# First_Board.net
KiCad netlist of a schematic drawn in EAGLE
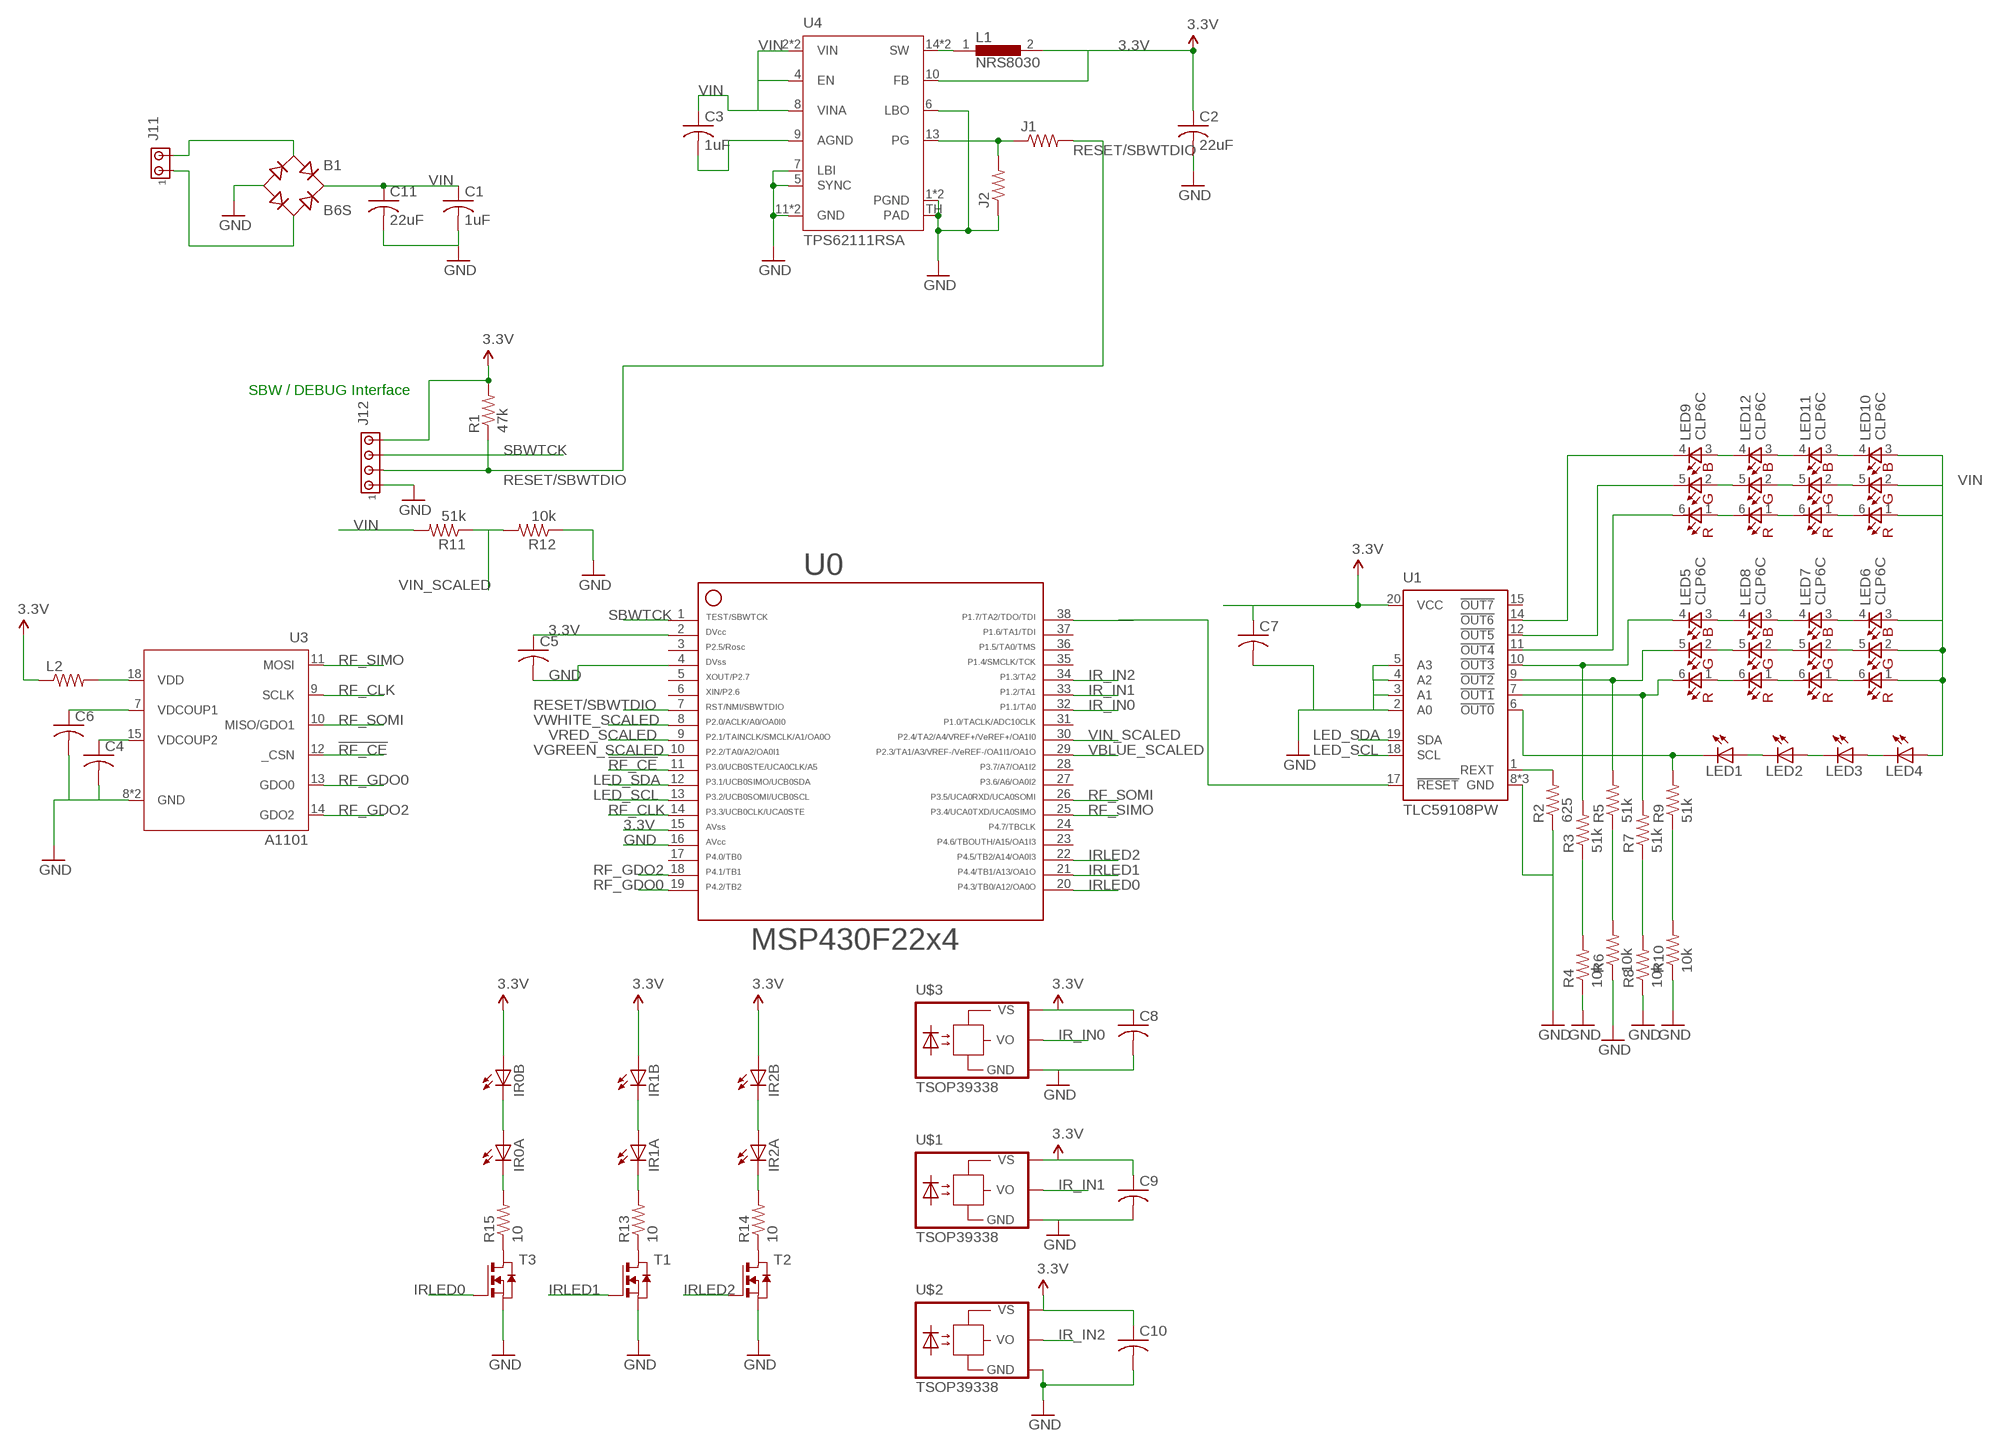
[diagram p0: schematic, sheet 1]

(export (version "E")
  (design (tool "Eeschema 10.0.6"))
  (components
    (comp (ref "B1")
      (value "B6S")
      (footprint "eagle-import:MBS")
      (libsource (lib "eagle-import") (part "BS6"))
    )
    (comp (ref "C1")
      (value "1uF")
      (footprint "eagle-import:C0805")
      (libsource (lib "eagle-import") (part "C-USC0805"))
    )
    (comp (ref "C2")
      (value "22uF")
      (footprint "eagle-import:C0805")
      (libsource (lib "eagle-import") (part "C-USC0805"))
    )
    (comp (ref "C3")
      (value "1uF")
      (footprint "eagle-import:C0603")
      (libsource (lib "eagle-import") (part "C-USC0603"))
    )
    (comp (ref "C4")
      (value "C-USC0603")
      (footprint "eagle-import:C0603")
      (libsource (lib "eagle-import") (part "C-USC0603"))
    )
    (comp (ref "C5")
      (value "C-USC0603")
      (footprint "eagle-import:C0603")
      (libsource (lib "eagle-import") (part "C-USC0603"))
    )
    (comp (ref "C6")
      (value "C-USC0603")
      (footprint "eagle-import:C0603")
      (libsource (lib "eagle-import") (part "C-USC0603"))
    )
    (comp (ref "C7")
      (value "C-USC0603")
      (footprint "eagle-import:C0603")
      (libsource (lib "eagle-import") (part "C-USC0603"))
    )
    (comp (ref "C8")
      (value "C-USC0603")
      (footprint "eagle-import:C0603")
      (libsource (lib "eagle-import") (part "C-USC0603"))
    )
    (comp (ref "C9")
      (value "C-USC0603")
      (footprint "eagle-import:C0603")
      (libsource (lib "eagle-import") (part "C-USC0603"))
    )
    (comp (ref "C10")
      (value "C-USC0603")
      (footprint "eagle-import:C0603")
      (libsource (lib "eagle-import") (part "C-USC0603"))
    )
    (comp (ref "C11")
      (value "22uF")
      (footprint "eagle-import:C1210")
      (libsource (lib "eagle-import") (part "C-USC1210"))
    )
    (comp (ref "IR0A")
      (value "LED5MM")
      (footprint "eagle-import:LED5MM")
      (libsource (lib "eagle-import") (part "LED5MM"))
    )
    (comp (ref "IR0B")
      (value "LED5MM")
      (footprint "eagle-import:LED5MM")
      (libsource (lib "eagle-import") (part "LED5MM"))
    )
    (comp (ref "IR1A")
      (value "LED5MM")
      (footprint "eagle-import:LED5MM")
      (libsource (lib "eagle-import") (part "LED5MM"))
    )
    (comp (ref "IR1B")
      (value "LED5MM")
      (footprint "eagle-import:LED5MM")
      (libsource (lib "eagle-import") (part "LED5MM"))
    )
    (comp (ref "IR2A")
      (value "LED5MM")
      (footprint "eagle-import:LED5MM")
      (libsource (lib "eagle-import") (part "LED5MM"))
    )
    (comp (ref "IR2B")
      (value "LED5MM")
      (footprint "eagle-import:LED5MM")
      (libsource (lib "eagle-import") (part "LED5MM"))
    )
    (comp (ref "J1")
      (value "R-US_R0603")
      (footprint "eagle-import:R0603")
      (libsource (lib "eagle-import") (part "R-US_R0603"))
    )
    (comp (ref "J2")
      (value "R-US_R0603")
      (footprint "eagle-import:R0603")
      (libsource (lib "eagle-import") (part "R-US_R0603"))
    )
    (comp (ref "J11")
      (value "MTA02-100")
      (footprint "eagle-import:10X02MTA")
      (libsource (lib "eagle-import") (part "MTA02-100"))
    )
    (comp (ref "J12")
      (value "MTA04-100")
      (footprint "eagle-import:10X04MTA")
      (libsource (lib "eagle-import") (part "MTA04-100"))
    )
    (comp (ref "L1")
      (value "NRS8030")
      (footprint "eagle-import:NRS8030")
      (libsource (lib "eagle-import") (part "NRS8030"))
    )
    (comp (ref "L2")
      (value "R-US_R0603")
      (footprint "eagle-import:R0603")
      (libsource (lib "eagle-import") (part "R-US_R0603"))
    )
    (comp (ref "LED1")
      (value "LED-2AC-SUPERFLUX")
      (footprint "eagle-import:SUPERFLUX-7.6X7.6")
      (libsource (lib "eagle-import") (part "LED-2AC-SUPERFLUX"))
    )
    (comp (ref "LED2")
      (value "LED-2AC-SUPERFLUX")
      (footprint "eagle-import:SUPERFLUX-7.6X7.6")
      (libsource (lib "eagle-import") (part "LED-2AC-SUPERFLUX"))
    )
    (comp (ref "LED3")
      (value "LED-2AC-SUPERFLUX")
      (footprint "eagle-import:SUPERFLUX-7.6X7.6")
      (libsource (lib "eagle-import") (part "LED-2AC-SUPERFLUX"))
    )
    (comp (ref "LED4")
      (value "LED-2AC-SUPERFLUX")
      (footprint "eagle-import:SUPERFLUX-7.6X7.6")
      (libsource (lib "eagle-import") (part "LED-2AC-SUPERFLUX"))
    )
    (comp (ref "LED5")
      (value "CLP6C")
      (footprint "eagle-import:CLP6C")
      (libsource (lib "eagle-import") (part "CLP6C"))
    )
    (comp (ref "LED6")
      (value "CLP6C")
      (footprint "eagle-import:CLP6C")
      (libsource (lib "eagle-import") (part "CLP6C"))
    )
    (comp (ref "LED7")
      (value "CLP6C")
      (footprint "eagle-import:CLP6C")
      (libsource (lib "eagle-import") (part "CLP6C"))
    )
    (comp (ref "LED8")
      (value "CLP6C")
      (footprint "eagle-import:CLP6C")
      (libsource (lib "eagle-import") (part "CLP6C"))
    )
    (comp (ref "LED9")
      (value "CLP6C")
      (footprint "eagle-import:CLP6C")
      (libsource (lib "eagle-import") (part "CLP6C"))
    )
    (comp (ref "LED10")
      (value "CLP6C")
      (footprint "eagle-import:CLP6C")
      (libsource (lib "eagle-import") (part "CLP6C"))
    )
    (comp (ref "LED11")
      (value "CLP6C")
      (footprint "eagle-import:CLP6C")
      (libsource (lib "eagle-import") (part "CLP6C"))
    )
    (comp (ref "LED12")
      (value "CLP6C")
      (footprint "eagle-import:CLP6C")
      (libsource (lib "eagle-import") (part "CLP6C"))
    )
    (comp (ref "R1")
      (value "47k")
      (footprint "eagle-import:R0603")
      (libsource (lib "eagle-import") (part "R-US_R0603"))
    )
    (comp (ref "R2")
      (value "625")
      (footprint "eagle-import:R0603")
      (libsource (lib "eagle-import") (part "R-US_R0603"))
    )
    (comp (ref "R3")
      (value "51k")
      (footprint "eagle-import:R0603")
      (libsource (lib "eagle-import") (part "R-US_R0603"))
    )
    (comp (ref "R4")
      (value "10k")
      (footprint "eagle-import:R0603")
      (libsource (lib "eagle-import") (part "R-US_R0603"))
    )
    (comp (ref "R5")
      (value "51k")
      (footprint "eagle-import:R0603")
      (libsource (lib "eagle-import") (part "R-US_R0603"))
    )
    (comp (ref "R6")
      (value "10k")
      (footprint "eagle-import:R0603")
      (libsource (lib "eagle-import") (part "R-US_R0603"))
    )
    (comp (ref "R7")
      (value "51k")
      (footprint "eagle-import:R0603")
      (libsource (lib "eagle-import") (part "R-US_R0603"))
    )
    (comp (ref "R8")
      (value "10k")
      (footprint "eagle-import:R0603")
      (libsource (lib "eagle-import") (part "R-US_R0603"))
    )
    (comp (ref "R9")
      (value "51k")
      (footprint "eagle-import:R0603")
      (libsource (lib "eagle-import") (part "R-US_R0603"))
    )
    (comp (ref "R10")
      (value "10k")
      (footprint "eagle-import:R0603")
      (libsource (lib "eagle-import") (part "R-US_R0603"))
    )
    (comp (ref "R11")
      (value "51k")
      (footprint "eagle-import:R0603")
      (libsource (lib "eagle-import") (part "R-US_R0603"))
    )
    (comp (ref "R12")
      (value "10k")
      (footprint "eagle-import:R0603")
      (libsource (lib "eagle-import") (part "R-US_R0603"))
    )
    (comp (ref "R13")
      (value "10")
      (footprint "eagle-import:R0603")
      (libsource (lib "eagle-import") (part "R-US_R0603"))
    )
    (comp (ref "R14")
      (value "10")
      (footprint "eagle-import:R0603")
      (libsource (lib "eagle-import") (part "R-US_R0603"))
    )
    (comp (ref "R15")
      (value "10")
      (footprint "eagle-import:R0603")
      (libsource (lib "eagle-import") (part "R-US_R0603"))
    )
    (comp (ref "T1")
      (value "NMOSSOT23")
      (footprint "eagle-import:SOT-23")
      (libsource (lib "eagle-import") (part "NMOSSOT23"))
    )
    (comp (ref "T2")
      (value "NMOSSOT23")
      (footprint "eagle-import:SOT-23")
      (libsource (lib "eagle-import") (part "NMOSSOT23"))
    )
    (comp (ref "T3")
      (value "NMOSSOT23")
      (footprint "eagle-import:SOT-23")
      (libsource (lib "eagle-import") (part "NMOSSOT23"))
    )
    (comp (ref "U$1")
      (value "TSOP39338")
      (footprint "eagle-import:TSOP39338")
      (libsource (lib "eagle-import") (part "TSOP39338"))
    )
    (comp (ref "U$2")
      (value "TSOP39338")
      (footprint "eagle-import:TSOP39338")
      (libsource (lib "eagle-import") (part "TSOP39338"))
    )
    (comp (ref "U$3")
      (value "TSOP39338")
      (footprint "eagle-import:TSOP39338")
      (libsource (lib "eagle-import") (part "TSOP39338"))
    )
    (comp (ref "U0")
      (value "F22X4---DA38")
      (footprint "eagle-import:DA38")
      (libsource (lib "eagle-import") (part "F22X4---DA38"))
    )
    (comp (ref "U1")
      (value "TLC59108PW")
      (footprint "eagle-import:PW_R-PDSO-G20")
      (libsource (lib "eagle-import") (part "TLC59108PW"))
    )
    (comp (ref "U3")
      (value "A1101")
      (footprint "eagle-import:A1101")
      (libsource (lib "eagle-import") (part "A1101"))
    )
    (comp (ref "U4")
      (value "TPS62111RSA")
      (footprint "eagle-import:S-PVQFN-N16")
      (libsource (lib "eagle-import") (part "TPS62111RSA"))
    )
  )
  (nets
    (net (code "1") (name "/IRLED0") (class "Default")
      (node (ref "T3") (pin "3") (pinfunction "G_3") (pintype "passive"))
      (node (ref "U0") (pin "20") (pinfunction "20_20") (pintype "bidirectional"))
    )
    (net (code "2") (name "/IRLED1") (class "Default")
      (node (ref "T1") (pin "3") (pinfunction "G_3") (pintype "passive"))
      (node (ref "U0") (pin "21") (pinfunction "21_21") (pintype "bidirectional"))
    )
    (net (code "3") (name "/IRLED2") (class "Default")
      (node (ref "T2") (pin "3") (pinfunction "G_3") (pintype "passive"))
      (node (ref "U0") (pin "22") (pinfunction "22_22") (pintype "bidirectional"))
    )
    (net (code "4") (name "/IR_IN0") (class "Default")
      (node (ref "U$3") (pin "OUT") (pinfunction "VO_OUT") (pintype "open_collector"))
      (node (ref "U0") (pin "32") (pinfunction "32_32") (pintype "bidirectional"))
    )
    (net (code "5") (name "/IR_IN1") (class "Default")
      (node (ref "U$1") (pin "OUT") (pinfunction "VO_OUT") (pintype "open_collector"))
      (node (ref "U0") (pin "33") (pinfunction "33_33") (pintype "bidirectional"))
    )
    (net (code "6") (name "/IR_IN2") (class "Default")
      (node (ref "U$2") (pin "OUT") (pinfunction "VO_OUT") (pintype "open_collector"))
      (node (ref "U0") (pin "34") (pinfunction "34_34") (pintype "bidirectional"))
    )
    (net (code "7") (name "/LED_SCL") (class "Default")
      (node (ref "U0") (pin "13") (pinfunction "13_13") (pintype "bidirectional"))
      (node (ref "U1") (pin "18") (pinfunction "SCL_18") (pintype "bidirectional"))
    )
    (net (code "8") (name "/LED_SDA") (class "Default")
      (node (ref "U0") (pin "12") (pinfunction "12_12") (pintype "bidirectional"))
      (node (ref "U1") (pin "19") (pinfunction "SDA_19") (pintype "bidirectional"))
    )
    (net (code "9") (name "/RESET{slash}SBWTDIO") (class "Default")
      (node (ref "J1") (pin "2") (pinfunction "2_2") (pintype "passive"))
      (node (ref "J12") (pin "2") (pinfunction "2_2") (pintype "passive"))
      (node (ref "R1") (pin "1") (pinfunction "1_1") (pintype "passive"))
      (node (ref "U0") (pin "7") (pinfunction "7_7") (pintype "bidirectional"))
    )
    (net (code "10") (name "/RF_CLK") (class "Default")
      (node (ref "U0") (pin "14") (pinfunction "14_14") (pintype "bidirectional"))
      (node (ref "U3") (pin "9") (pinfunction "SCLK_9") (pintype "input"))
    )
    (net (code "11") (name "/RF_GDO0") (class "Default")
      (node (ref "U0") (pin "19") (pinfunction "19_19") (pintype "bidirectional"))
      (node (ref "U3") (pin "13") (pinfunction "GDO0_13") (pintype "input"))
    )
    (net (code "12") (name "/RF_GDO2") (class "Default")
      (node (ref "U0") (pin "18") (pinfunction "18_18") (pintype "bidirectional"))
      (node (ref "U3") (pin "14") (pinfunction "GDO2_14") (pintype "input"))
    )
    (net (code "13") (name "/RF_SIMO") (class "Default")
      (node (ref "U0") (pin "25") (pinfunction "25_25") (pintype "bidirectional"))
      (node (ref "U3") (pin "11") (pinfunction "MOSI_11") (pintype "input"))
    )
    (net (code "14") (name "/RF_SOMI") (class "Default")
      (node (ref "U0") (pin "26") (pinfunction "26_26") (pintype "bidirectional"))
      (node (ref "U3") (pin "10") (pinfunction "MISO/GDO1_10") (pintype "input"))
    )
    (net (code "15") (name "/SBWTCK") (class "Default")
      (node (ref "J12") (pin "3") (pinfunction "3_3") (pintype "passive"))
      (node (ref "U0") (pin "1") (pinfunction "1_1") (pintype "input"))
    )
    (net (code "16") (name "/VBLUE_SCALED") (class "Default")
      (node (ref "R3") (pin "1") (pinfunction "1_1") (pintype "passive"))
      (node (ref "R4") (pin "2") (pinfunction "2_2") (pintype "passive"))
      (node (ref "U0") (pin "29") (pinfunction "29_29") (pintype "bidirectional"))
    )
    (net (code "17") (name "/VGREEN_SCALED") (class "Default")
      (node (ref "R5") (pin "1") (pinfunction "1_1") (pintype "passive"))
      (node (ref "R6") (pin "2") (pinfunction "2_2") (pintype "passive"))
      (node (ref "U0") (pin "10") (pinfunction "10_10") (pintype "bidirectional"))
    )
    (net (code "18") (name "/VIN") (class "Default")
      (node (ref "B1") (pin "+") (pinfunction "+_+") (pintype "passive"))
      (node (ref "C1") (pin "1") (pinfunction "1_1") (pintype "passive"))
      (node (ref "C11") (pin "1") (pinfunction "1_1") (pintype "passive"))
      (node (ref "C3") (pin "1") (pinfunction "1_1") (pintype "passive"))
      (node (ref "LED10") (pin "1") (pinfunction "RA_1") (pintype "passive"))
      (node (ref "LED10") (pin "2") (pinfunction "GA_2") (pintype "passive"))
      (node (ref "LED10") (pin "3") (pinfunction "BA_3") (pintype "passive"))
      (node (ref "LED4") (pin "2") (pinfunction "A_2") (pintype "passive"))
      (node (ref "LED4") (pin "4") (pinfunction "A_4") (pintype "passive"))
      (node (ref "LED6") (pin "1") (pinfunction "RA_1") (pintype "passive"))
      (node (ref "LED6") (pin "2") (pinfunction "GA_2") (pintype "passive"))
      (node (ref "LED6") (pin "3") (pinfunction "BA_3") (pintype "passive"))
      (node (ref "R11") (pin "2") (pinfunction "2_2") (pintype "passive"))
      (node (ref "U4") (pin "2") (pinfunction "VIN_2") (pintype "input"))
      (node (ref "U4") (pin "3") (pinfunction "VIN_3") (pintype "input"))
      (node (ref "U4") (pin "4") (pinfunction "EN_4") (pintype "input"))
      (node (ref "U4") (pin "8") (pinfunction "VINA_8") (pintype "input"))
    )
    (net (code "19") (name "/VIN_SCALED") (class "Default")
      (node (ref "R11") (pin "1") (pinfunction "1_1") (pintype "passive"))
      (node (ref "R12") (pin "2") (pinfunction "2_2") (pintype "passive"))
      (node (ref "U0") (pin "30") (pinfunction "30_30") (pintype "bidirectional"))
    )
    (net (code "20") (name "/VRED_SCALED") (class "Default")
      (node (ref "R7") (pin "1") (pinfunction "1_1") (pintype "passive"))
      (node (ref "R8") (pin "2") (pinfunction "2_2") (pintype "passive"))
      (node (ref "U0") (pin "9") (pinfunction "9_9") (pintype "bidirectional"))
    )
    (net (code "21") (name "/VWHITE_SCALED") (class "Default")
      (node (ref "R10") (pin "2") (pinfunction "2_2") (pintype "passive"))
      (node (ref "R9") (pin "1") (pinfunction "1_1") (pintype "passive"))
      (node (ref "U0") (pin "8") (pinfunction "8_8") (pintype "bidirectional"))
    )
    (net (code "22") (name "/~{RF_CE}") (class "Default")
      (node (ref "U0") (pin "11") (pinfunction "11_11") (pintype "bidirectional"))
      (node (ref "U3") (pin "12") (pinfunction "_CSN_12") (pintype "input"))
    )
    (net (code "23") (name "3.3V") (class "Default")
      (node (ref "C10") (pin "1") (pinfunction "1_1") (pintype "passive"))
      (node (ref "C2") (pin "1") (pinfunction "1_1") (pintype "passive"))
      (node (ref "C5") (pin "1") (pinfunction "1_1") (pintype "passive"))
      (node (ref "C7") (pin "1") (pinfunction "1_1") (pintype "passive"))
      (node (ref "C8") (pin "1") (pinfunction "1_1") (pintype "passive"))
      (node (ref "C9") (pin "1") (pinfunction "1_1") (pintype "passive"))
      (node (ref "IR0B") (pin "A") (pinfunction "A_A") (pintype "passive"))
      (node (ref "IR1B") (pin "A") (pinfunction "A_A") (pintype "passive"))
      (node (ref "IR2B") (pin "A") (pinfunction "A_A") (pintype "passive"))
      (node (ref "J12") (pin "4") (pinfunction "4_4") (pintype "passive"))
      (node (ref "L1") (pin "2") (pinfunction "2_2") (pintype "passive"))
      (node (ref "L2") (pin "1") (pinfunction "1_1") (pintype "passive"))
      (node (ref "R1") (pin "2") (pinfunction "2_2") (pintype "passive"))
      (node (ref "U$1") (pin "VS") (pinfunction "VS_VS") (pintype "power_in"))
      (node (ref "U$2") (pin "VS") (pinfunction "VS_VS") (pintype "power_in"))
      (node (ref "U$3") (pin "VS") (pinfunction "VS_VS") (pintype "power_in"))
      (node (ref "U0") (pin "15") (pinfunction "15_15") (pintype "power_in"))
      (node (ref "U0") (pin "2") (pinfunction "2_2") (pintype "power_in"))
      (node (ref "U1") (pin "20") (pinfunction "VCC_20") (pintype "power_in"))
      (node (ref "U4") (pin "10") (pinfunction "FB_10") (pintype "input"))
    )
    (net (code "24") (name "GND") (class "Default")
      (node (ref "B1") (pin "-") (pinfunction "-_-") (pintype "passive"))
      (node (ref "C1") (pin "2") (pinfunction "2_2") (pintype "passive"))
      (node (ref "C10") (pin "2") (pinfunction "2_2") (pintype "passive"))
      (node (ref "C11") (pin "2") (pinfunction "2_2") (pintype "passive"))
      (node (ref "C2") (pin "2") (pinfunction "2_2") (pintype "passive"))
      (node (ref "C4") (pin "2") (pinfunction "2_2") (pintype "passive"))
      (node (ref "C5") (pin "2") (pinfunction "2_2") (pintype "passive"))
      (node (ref "C6") (pin "2") (pinfunction "2_2") (pintype "passive"))
      (node (ref "C7") (pin "2") (pinfunction "2_2") (pintype "passive"))
      (node (ref "C8") (pin "2") (pinfunction "2_2") (pintype "passive"))
      (node (ref "C9") (pin "2") (pinfunction "2_2") (pintype "passive"))
      (node (ref "J12") (pin "1") (pinfunction "1_1") (pintype "passive"))
      (node (ref "J2") (pin "1") (pinfunction "1_1") (pintype "passive"))
      (node (ref "R10") (pin "1") (pinfunction "1_1") (pintype "passive"))
      (node (ref "R12") (pin "1") (pinfunction "1_1") (pintype "passive"))
      (node (ref "R2") (pin "1") (pinfunction "1_1") (pintype "passive"))
      (node (ref "R4") (pin "1") (pinfunction "1_1") (pintype "passive"))
      (node (ref "R6") (pin "1") (pinfunction "1_1") (pintype "passive"))
      (node (ref "R8") (pin "1") (pinfunction "1_1") (pintype "passive"))
      (node (ref "T1") (pin "2") (pinfunction "S_2") (pintype "passive"))
      (node (ref "T2") (pin "2") (pinfunction "S_2") (pintype "passive"))
      (node (ref "T3") (pin "2") (pinfunction "S_2") (pintype "passive"))
      (node (ref "U$1") (pin "GND") (pinfunction "GND_GND") (pintype "power_in"))
      (node (ref "U$2") (pin "GND") (pinfunction "GND_GND") (pintype "power_in"))
      (node (ref "U$3") (pin "GND") (pinfunction "GND_GND") (pintype "power_in"))
      (node (ref "U0") (pin "16") (pinfunction "16_16") (pintype "power_in"))
      (node (ref "U0") (pin "4") (pinfunction "4_4") (pintype "power_in"))
      (node (ref "U1") (pin "13") (pinfunction "GND_13") (pintype "power_in"))
      (node (ref "U1") (pin "16") (pinfunction "GND_16") (pintype "power_in"))
      (node (ref "U1") (pin "2") (pinfunction "A0_2") (pintype "input"))
      (node (ref "U1") (pin "3") (pinfunction "A1_3") (pintype "input"))
      (node (ref "U1") (pin "4") (pinfunction "A2_4") (pintype "input"))
      (node (ref "U1") (pin "5") (pinfunction "A3_5") (pintype "input"))
      (node (ref "U1") (pin "8") (pinfunction "GND_8") (pintype "power_in"))
      (node (ref "U3") (pin "17") (pinfunction "GND_17") (pintype "power_in"))
      (node (ref "U3") (pin "8") (pinfunction "GND_8") (pintype "power_in"))
      (node (ref "U4") (pin "1") (pinfunction "PGND_1") (pintype "passive"))
      (node (ref "U4") (pin "11") (pinfunction "GND_11") (pintype "power_in"))
      (node (ref "U4") (pin "12") (pinfunction "GND_12") (pintype "power_in"))
      (node (ref "U4") (pin "16") (pinfunction "PGND_16") (pintype "passive"))
      (node (ref "U4") (pin "5") (pinfunction "SYNC_5") (pintype "input"))
      (node (ref "U4") (pin "6") (pinfunction "LBO_6") (pintype "passive"))
      (node (ref "U4") (pin "7") (pinfunction "LBI_7") (pintype "input"))
      (node (ref "U4") (pin "TH") (pinfunction "PAD_TH") (pintype "passive"))
    )
    (net (code "25") (name "Net-(B1-PadAC1)") (class "Default")
      (node (ref "B1") (pin "AC1") (pinfunction "AC1_AC1") (pintype "passive"))
      (node (ref "J11") (pin "2") (pinfunction "2_2") (pintype "passive"))
    )
    (net (code "26") (name "Net-(B1-PadAC2)") (class "Default")
      (node (ref "B1") (pin "AC2") (pinfunction "AC2_AC2") (pintype "passive"))
      (node (ref "J11") (pin "1") (pinfunction "1_1") (pintype "passive"))
    )
    (net (code "27") (name "Net-(IR0A-C)") (class "Default")
      (node (ref "IR0A") (pin "K") (pinfunction "C_K") (pintype "passive"))
      (node (ref "R15") (pin "2") (pinfunction "2_2") (pintype "passive"))
    )
    (net (code "28") (name "Net-(IR0B-C)") (class "Default")
      (node (ref "IR0A") (pin "A") (pinfunction "A_A") (pintype "passive"))
      (node (ref "IR0B") (pin "K") (pinfunction "C_K") (pintype "passive"))
    )
    (net (code "29") (name "Net-(IR1A-C)") (class "Default")
      (node (ref "IR1A") (pin "K") (pinfunction "C_K") (pintype "passive"))
      (node (ref "R13") (pin "2") (pinfunction "2_2") (pintype "passive"))
    )
    (net (code "30") (name "Net-(IR1B-C)") (class "Default")
      (node (ref "IR1A") (pin "A") (pinfunction "A_A") (pintype "passive"))
      (node (ref "IR1B") (pin "K") (pinfunction "C_K") (pintype "passive"))
    )
    (net (code "31") (name "Net-(IR2A-C)") (class "Default")
      (node (ref "IR2A") (pin "K") (pinfunction "C_K") (pintype "passive"))
      (node (ref "R14") (pin "2") (pinfunction "2_2") (pintype "passive"))
    )
    (net (code "32") (name "Net-(IR2B-C)") (class "Default")
      (node (ref "IR2A") (pin "A") (pinfunction "A_A") (pintype "passive"))
      (node (ref "IR2B") (pin "K") (pinfunction "C_K") (pintype "passive"))
    )
    (net (code "33") (name "Net-(L1-Pad1)") (class "Default")
      (node (ref "L1") (pin "1") (pinfunction "1_1") (pintype "passive"))
      (node (ref "U4") (pin "14") (pinfunction "SW_14") (pintype "output"))
      (node (ref "U4") (pin "15") (pinfunction "SW_15") (pintype "output"))
    )
    (net (code "34") (name "Net-(LED1-A-Pad2)") (class "Default")
      (node (ref "LED1") (pin "2") (pinfunction "A_2") (pintype "passive"))
      (node (ref "LED1") (pin "4") (pinfunction "A_4") (pintype "passive"))
      (node (ref "LED2") (pin "1") (pinfunction "C_1") (pintype "passive"))
      (node (ref "LED2") (pin "3") (pinfunction "C_3") (pintype "passive"))
    )
    (net (code "35") (name "Net-(LED2-A-Pad2)") (class "Default")
      (node (ref "LED2") (pin "2") (pinfunction "A_2") (pintype "passive"))
      (node (ref "LED2") (pin "4") (pinfunction "A_4") (pintype "passive"))
      (node (ref "LED3") (pin "1") (pinfunction "C_1") (pintype "passive"))
      (node (ref "LED3") (pin "3") (pinfunction "C_3") (pintype "passive"))
    )
    (net (code "36") (name "Net-(LED3-A-Pad2)") (class "Default")
      (node (ref "LED3") (pin "2") (pinfunction "A_2") (pintype "passive"))
      (node (ref "LED3") (pin "4") (pinfunction "A_4") (pintype "passive"))
      (node (ref "LED4") (pin "1") (pinfunction "C_1") (pintype "passive"))
      (node (ref "LED4") (pin "3") (pinfunction "C_3") (pintype "passive"))
    )
    (net (code "37") (name "Net-(LED5-BA)") (class "Default")
      (node (ref "LED5") (pin "3") (pinfunction "BA_3") (pintype "passive"))
      (node (ref "LED8") (pin "4") (pinfunction "BC_4") (pintype "passive"))
    )
    (net (code "38") (name "Net-(LED5-BC)") (class "Default")
      (node (ref "LED5") (pin "4") (pinfunction "BC_4") (pintype "passive"))
      (node (ref "R3") (pin "2") (pinfunction "2_2") (pintype "passive"))
      (node (ref "U1") (pin "10") (pinfunction "~{OUT3}_10") (pintype "output"))
    )
    (net (code "39") (name "Net-(LED5-GA)") (class "Default")
      (node (ref "LED5") (pin "2") (pinfunction "GA_2") (pintype "passive"))
      (node (ref "LED8") (pin "5") (pinfunction "GC_5") (pintype "passive"))
    )
    (net (code "40") (name "Net-(LED5-GC)") (class "Default")
      (node (ref "LED5") (pin "5") (pinfunction "GC_5") (pintype "passive"))
      (node (ref "R5") (pin "2") (pinfunction "2_2") (pintype "passive"))
      (node (ref "U1") (pin "9") (pinfunction "~{OUT2}_9") (pintype "output"))
    )
    (net (code "41") (name "Net-(LED5-RA)") (class "Default")
      (node (ref "LED5") (pin "1") (pinfunction "RA_1") (pintype "passive"))
      (node (ref "LED8") (pin "6") (pinfunction "RC_6") (pintype "passive"))
    )
    (net (code "42") (name "Net-(LED5-RC)") (class "Default")
      (node (ref "LED5") (pin "6") (pinfunction "RC_6") (pintype "passive"))
      (node (ref "R7") (pin "2") (pinfunction "2_2") (pintype "passive"))
      (node (ref "U1") (pin "7") (pinfunction "~{OUT1}_7") (pintype "output"))
    )
    (net (code "43") (name "Net-(LED6-BC)") (class "Default")
      (node (ref "LED6") (pin "4") (pinfunction "BC_4") (pintype "passive"))
      (node (ref "LED7") (pin "3") (pinfunction "BA_3") (pintype "passive"))
    )
    (net (code "44") (name "Net-(LED6-GC)") (class "Default")
      (node (ref "LED6") (pin "5") (pinfunction "GC_5") (pintype "passive"))
      (node (ref "LED7") (pin "2") (pinfunction "GA_2") (pintype "passive"))
    )
    (net (code "45") (name "Net-(LED6-RC)") (class "Default")
      (node (ref "LED6") (pin "6") (pinfunction "RC_6") (pintype "passive"))
      (node (ref "LED7") (pin "1") (pinfunction "RA_1") (pintype "passive"))
    )
    (net (code "46") (name "Net-(LED7-BC)") (class "Default")
      (node (ref "LED7") (pin "4") (pinfunction "BC_4") (pintype "passive"))
      (node (ref "LED8") (pin "3") (pinfunction "BA_3") (pintype "passive"))
    )
    (net (code "47") (name "Net-(LED7-GC)") (class "Default")
      (node (ref "LED7") (pin "5") (pinfunction "GC_5") (pintype "passive"))
      (node (ref "LED8") (pin "2") (pinfunction "GA_2") (pintype "passive"))
    )
    (net (code "48") (name "Net-(LED7-RC)") (class "Default")
      (node (ref "LED7") (pin "6") (pinfunction "RC_6") (pintype "passive"))
      (node (ref "LED8") (pin "1") (pinfunction "RA_1") (pintype "passive"))
    )
    (net (code "49") (name "Net-(LED9-BC)") (class "Default")
      (node (ref "LED9") (pin "4") (pinfunction "BC_4") (pintype "passive"))
      (node (ref "U1") (pin "14") (pinfunction "~{OUT6}_14") (pintype "output"))
    )
    (net (code "50") (name "Net-(LED9-GC)") (class "Default")
      (node (ref "LED9") (pin "5") (pinfunction "GC_5") (pintype "passive"))
      (node (ref "U1") (pin "12") (pinfunction "~{OUT5}_12") (pintype "output"))
    )
    (net (code "51") (name "Net-(LED9-RC)") (class "Default")
      (node (ref "LED9") (pin "6") (pinfunction "RC_6") (pintype "passive"))
      (node (ref "U1") (pin "11") (pinfunction "~{OUT4}_11") (pintype "output"))
    )
    (net (code "52") (name "Net-(LED10-BC)") (class "Default")
      (node (ref "LED10") (pin "4") (pinfunction "BC_4") (pintype "passive"))
      (node (ref "LED11") (pin "3") (pinfunction "BA_3") (pintype "passive"))
    )
    (net (code "53") (name "Net-(LED10-GC)") (class "Default")
      (node (ref "LED10") (pin "5") (pinfunction "GC_5") (pintype "passive"))
      (node (ref "LED11") (pin "2") (pinfunction "GA_2") (pintype "passive"))
    )
    (net (code "54") (name "Net-(LED10-RC)") (class "Default")
      (node (ref "LED10") (pin "6") (pinfunction "RC_6") (pintype "passive"))
      (node (ref "LED11") (pin "1") (pinfunction "RA_1") (pintype "passive"))
    )
    (net (code "55") (name "Net-(LED11-BC)") (class "Default")
      (node (ref "LED11") (pin "4") (pinfunction "BC_4") (pintype "passive"))
      (node (ref "LED12") (pin "3") (pinfunction "BA_3") (pintype "passive"))
    )
    (net (code "56") (name "Net-(LED11-GC)") (class "Default")
      (node (ref "LED11") (pin "5") (pinfunction "GC_5") (pintype "passive"))
      (node (ref "LED12") (pin "2") (pinfunction "GA_2") (pintype "passive"))
    )
    (net (code "57") (name "Net-(LED11-RC)") (class "Default")
      (node (ref "LED11") (pin "6") (pinfunction "RC_6") (pintype "passive"))
      (node (ref "LED12") (pin "1") (pinfunction "RA_1") (pintype "passive"))
    )
    (net (code "58") (name "Net-(LED12-BC)") (class "Default")
      (node (ref "LED12") (pin "4") (pinfunction "BC_4") (pintype "passive"))
      (node (ref "LED9") (pin "3") (pinfunction "BA_3") (pintype "passive"))
    )
    (net (code "59") (name "Net-(LED12-GC)") (class "Default")
      (node (ref "LED12") (pin "5") (pinfunction "GC_5") (pintype "passive"))
      (node (ref "LED9") (pin "2") (pinfunction "GA_2") (pintype "passive"))
    )
    (net (code "60") (name "Net-(LED12-RC)") (class "Default")
      (node (ref "LED12") (pin "6") (pinfunction "RC_6") (pintype "passive"))
      (node (ref "LED9") (pin "1") (pinfunction "RA_1") (pintype "passive"))
    )
    (net (code "61") (name "Net-(T1-D)") (class "Default")
      (node (ref "R13") (pin "1") (pinfunction "1_1") (pintype "passive"))
      (node (ref "T1") (pin "1") (pinfunction "D_1") (pintype "passive"))
    )
    (net (code "62") (name "Net-(T2-D)") (class "Default")
      (node (ref "R14") (pin "1") (pinfunction "1_1") (pintype "passive"))
      (node (ref "T2") (pin "1") (pinfunction "D_1") (pintype "passive"))
    )
    (net (code "63") (name "Net-(T3-D)") (class "Default")
      (node (ref "R15") (pin "1") (pinfunction "1_1") (pintype "passive"))
      (node (ref "T3") (pin "1") (pinfunction "D_1") (pintype "passive"))
    )
    (net (code "64") (name "Net-(U1-REXT)") (class "Default")
      (node (ref "R2") (pin "2") (pinfunction "2_2") (pintype "passive"))
      (node (ref "U1") (pin "1") (pinfunction "REXT_1") (pintype "passive"))
    )
    (net (code "65") (name "Net-(U1-~{OUT0})") (class "Default")
      (node (ref "LED1") (pin "1") (pinfunction "C_1") (pintype "passive"))
      (node (ref "LED1") (pin "3") (pinfunction "C_3") (pintype "passive"))
      (node (ref "R9") (pin "2") (pinfunction "2_2") (pintype "passive"))
      (node (ref "U1") (pin "6") (pinfunction "~{OUT0}_6") (pintype "output"))
    )
    (net (code "66") (name "Net-(U3-VDCOUP1)") (class "Default")
      (node (ref "C6") (pin "1") (pinfunction "1_1") (pintype "passive"))
      (node (ref "U3") (pin "7") (pinfunction "VDCOUP1_7") (pintype "input"))
    )
    (net (code "67") (name "Net-(U3-VDCOUP2)") (class "Default")
      (node (ref "C4") (pin "1") (pinfunction "1_1") (pintype "passive"))
      (node (ref "U3") (pin "15") (pinfunction "VDCOUP2_15") (pintype "passive"))
    )
    (net (code "68") (name "Net-(U3-VDD)") (class "Default")
      (node (ref "L2") (pin "2") (pinfunction "2_2") (pintype "passive"))
      (node (ref "U3") (pin "18") (pinfunction "VDD_18") (pintype "output"))
    )
    (net (code "69") (name "Net-(U4-AGND)") (class "Default")
      (node (ref "C3") (pin "2") (pinfunction "2_2") (pintype "passive"))
      (node (ref "U4") (pin "9") (pinfunction "AGND_9") (pintype "input"))
    )
    (net (code "70") (name "Net-(U4-PG)") (class "Default")
      (node (ref "J1") (pin "1") (pinfunction "1_1") (pintype "passive"))
      (node (ref "J2") (pin "2") (pinfunction "2_2") (pintype "passive"))
      (node (ref "U4") (pin "13") (pinfunction "PG_13") (pintype "passive"))
    )
    (net (code "71") (name "unconnected-(U0-Pad3)") (class "Default")
      (node (ref "U0") (pin "3") (pinfunction "3_3") (pintype "bidirectional"))
    )
    (net (code "72") (name "unconnected-(U0-Pad5)") (class "Default")
      (node (ref "U0") (pin "5") (pinfunction "5_5") (pintype "bidirectional"))
    )
    (net (code "73") (name "unconnected-(U0-Pad6)") (class "Default")
      (node (ref "U0") (pin "6") (pinfunction "6_6") (pintype "bidirectional"))
    )
    (net (code "74") (name "unconnected-(U0-Pad17)") (class "Default")
      (node (ref "U0") (pin "17") (pinfunction "17_17") (pintype "bidirectional"))
    )
    (net (code "75") (name "unconnected-(U0-Pad23)") (class "Default")
      (node (ref "U0") (pin "23") (pinfunction "23_23") (pintype "bidirectional"))
    )
    (net (code "76") (name "unconnected-(U0-Pad24)") (class "Default")
      (node (ref "U0") (pin "24") (pinfunction "24_24") (pintype "bidirectional"))
    )
    (net (code "77") (name "unconnected-(U0-Pad27)") (class "Default")
      (node (ref "U0") (pin "27") (pinfunction "27_27") (pintype "bidirectional"))
    )
    (net (code "78") (name "unconnected-(U0-Pad28)") (class "Default")
      (node (ref "U0") (pin "28") (pinfunction "28_28") (pintype "bidirectional"))
    )
    (net (code "79") (name "unconnected-(U0-Pad31)") (class "Default")
      (node (ref "U0") (pin "31") (pinfunction "31_31") (pintype "bidirectional"))
    )
    (net (code "80") (name "unconnected-(U0-Pad35)") (class "Default")
      (node (ref "U0") (pin "35") (pinfunction "35_35") (pintype "bidirectional"))
    )
    (net (code "81") (name "unconnected-(U0-Pad36)") (class "Default")
      (node (ref "U0") (pin "36") (pinfunction "36_36") (pintype "bidirectional"))
    )
    (net (code "82") (name "unconnected-(U0-Pad37)") (class "Default")
      (node (ref "U0") (pin "37") (pinfunction "37_37") (pintype "bidirectional"))
    )
    (net (code "83") (name "unconnected-(U0-Pad38)") (class "Default")
      (node (ref "U0") (pin "38") (pinfunction "38_38") (pintype "bidirectional"))
    )
    (net (code "84") (name "unconnected-(U1-~{OUT7}-Pad15)") (class "Default")
      (node (ref "U1") (pin "15") (pinfunction "~{OUT7}_15") (pintype "output"))
    )
    (net (code "85") (name "unconnected-(U1-~{RESET}-Pad17)") (class "Default")
      (node (ref "U1") (pin "17") (pinfunction "~{RESET}_17") (pintype "input"))
    )
  )
)
